# Backplane.net
KiCad netlist of a schematic drawn in EAGLE
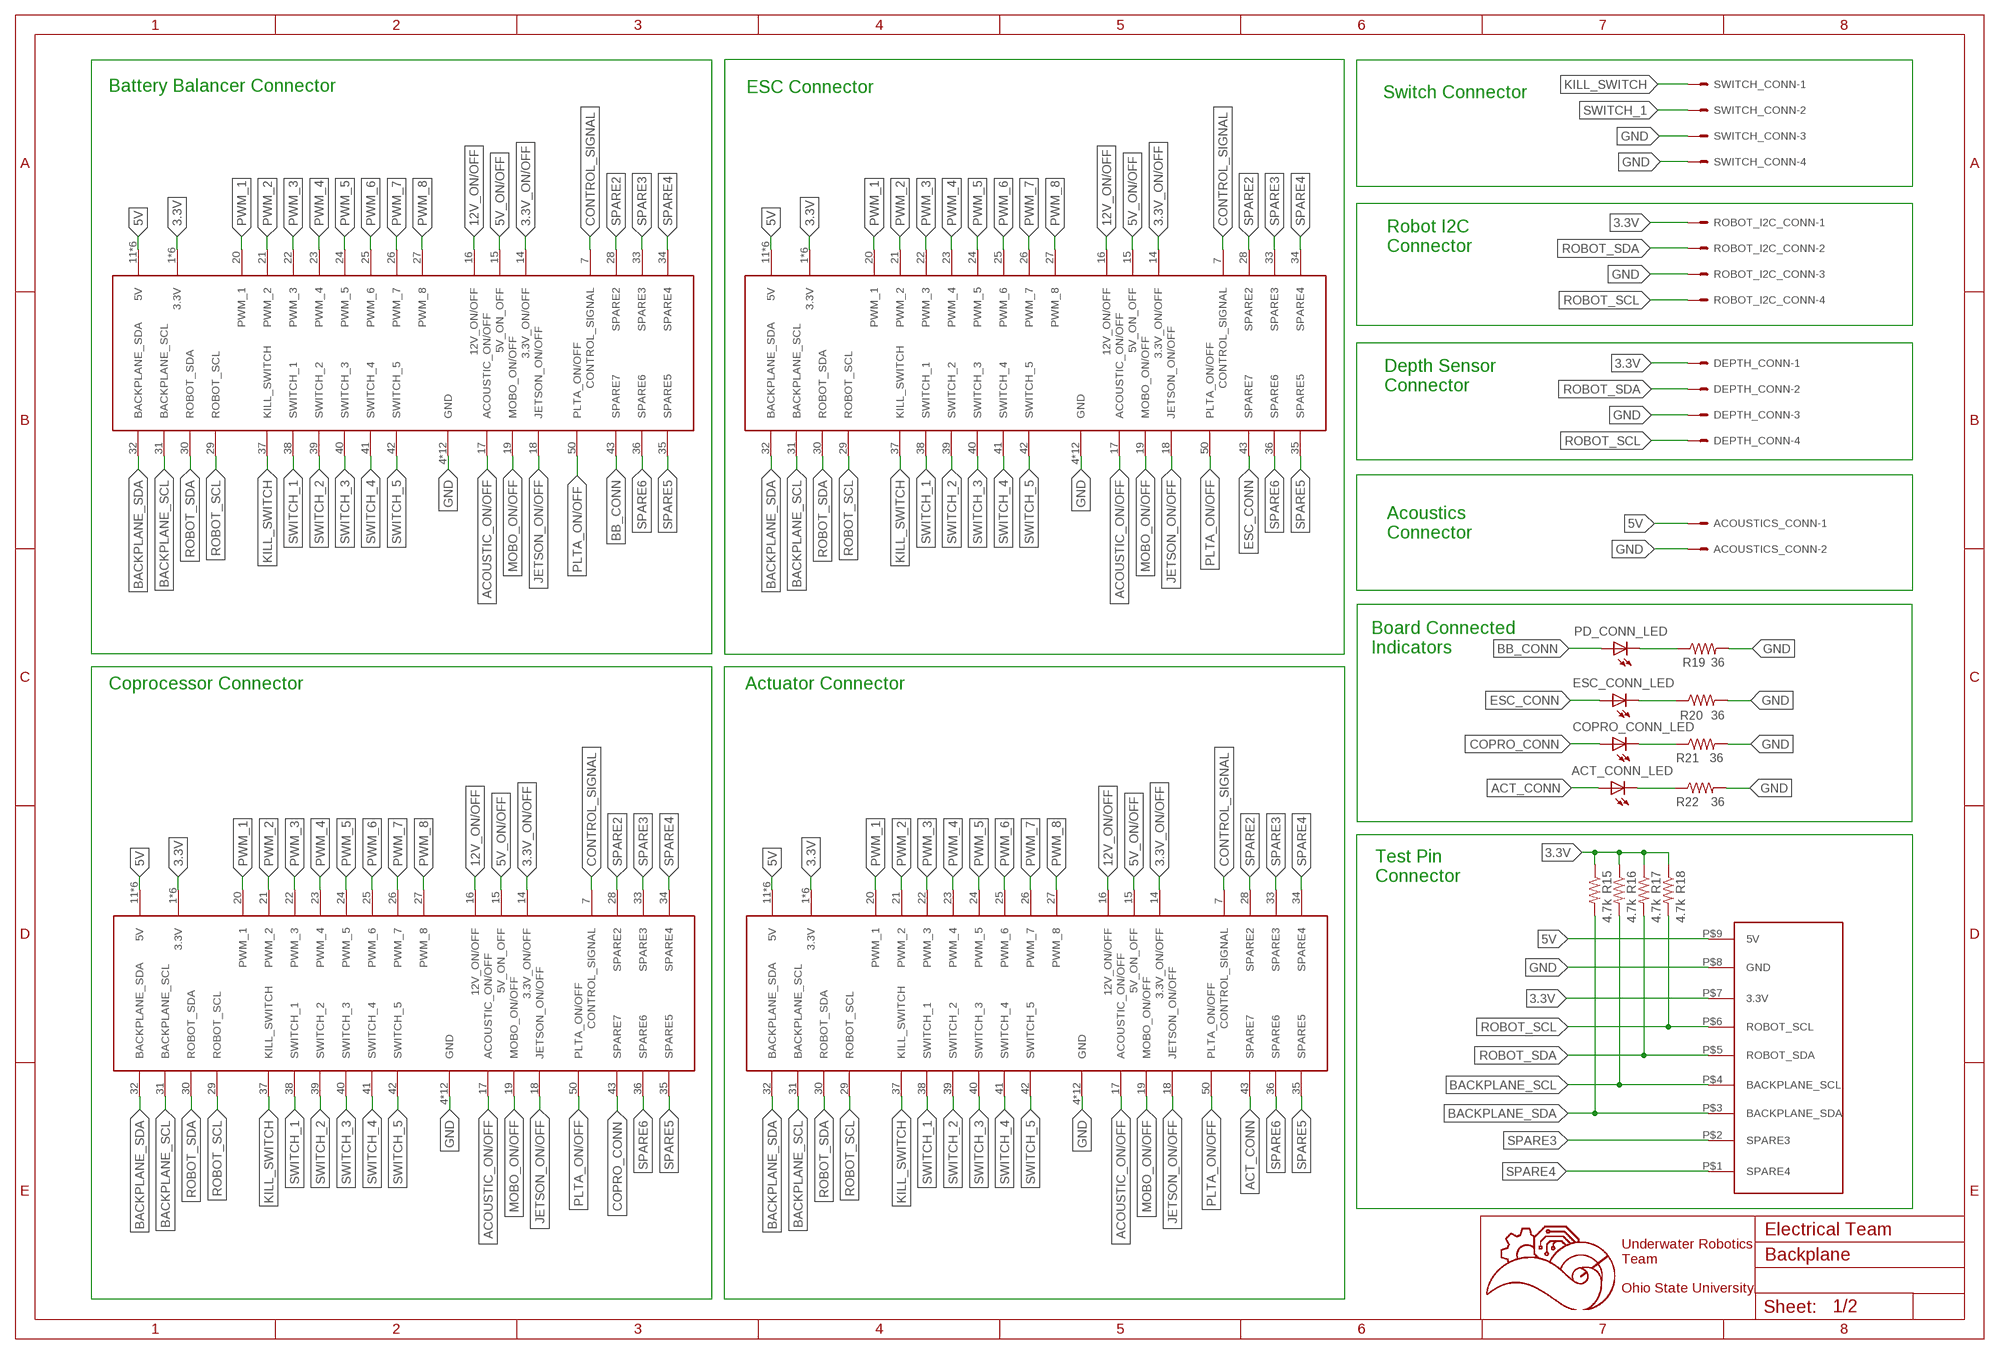
[diagram p0: schematic, sheet 1]
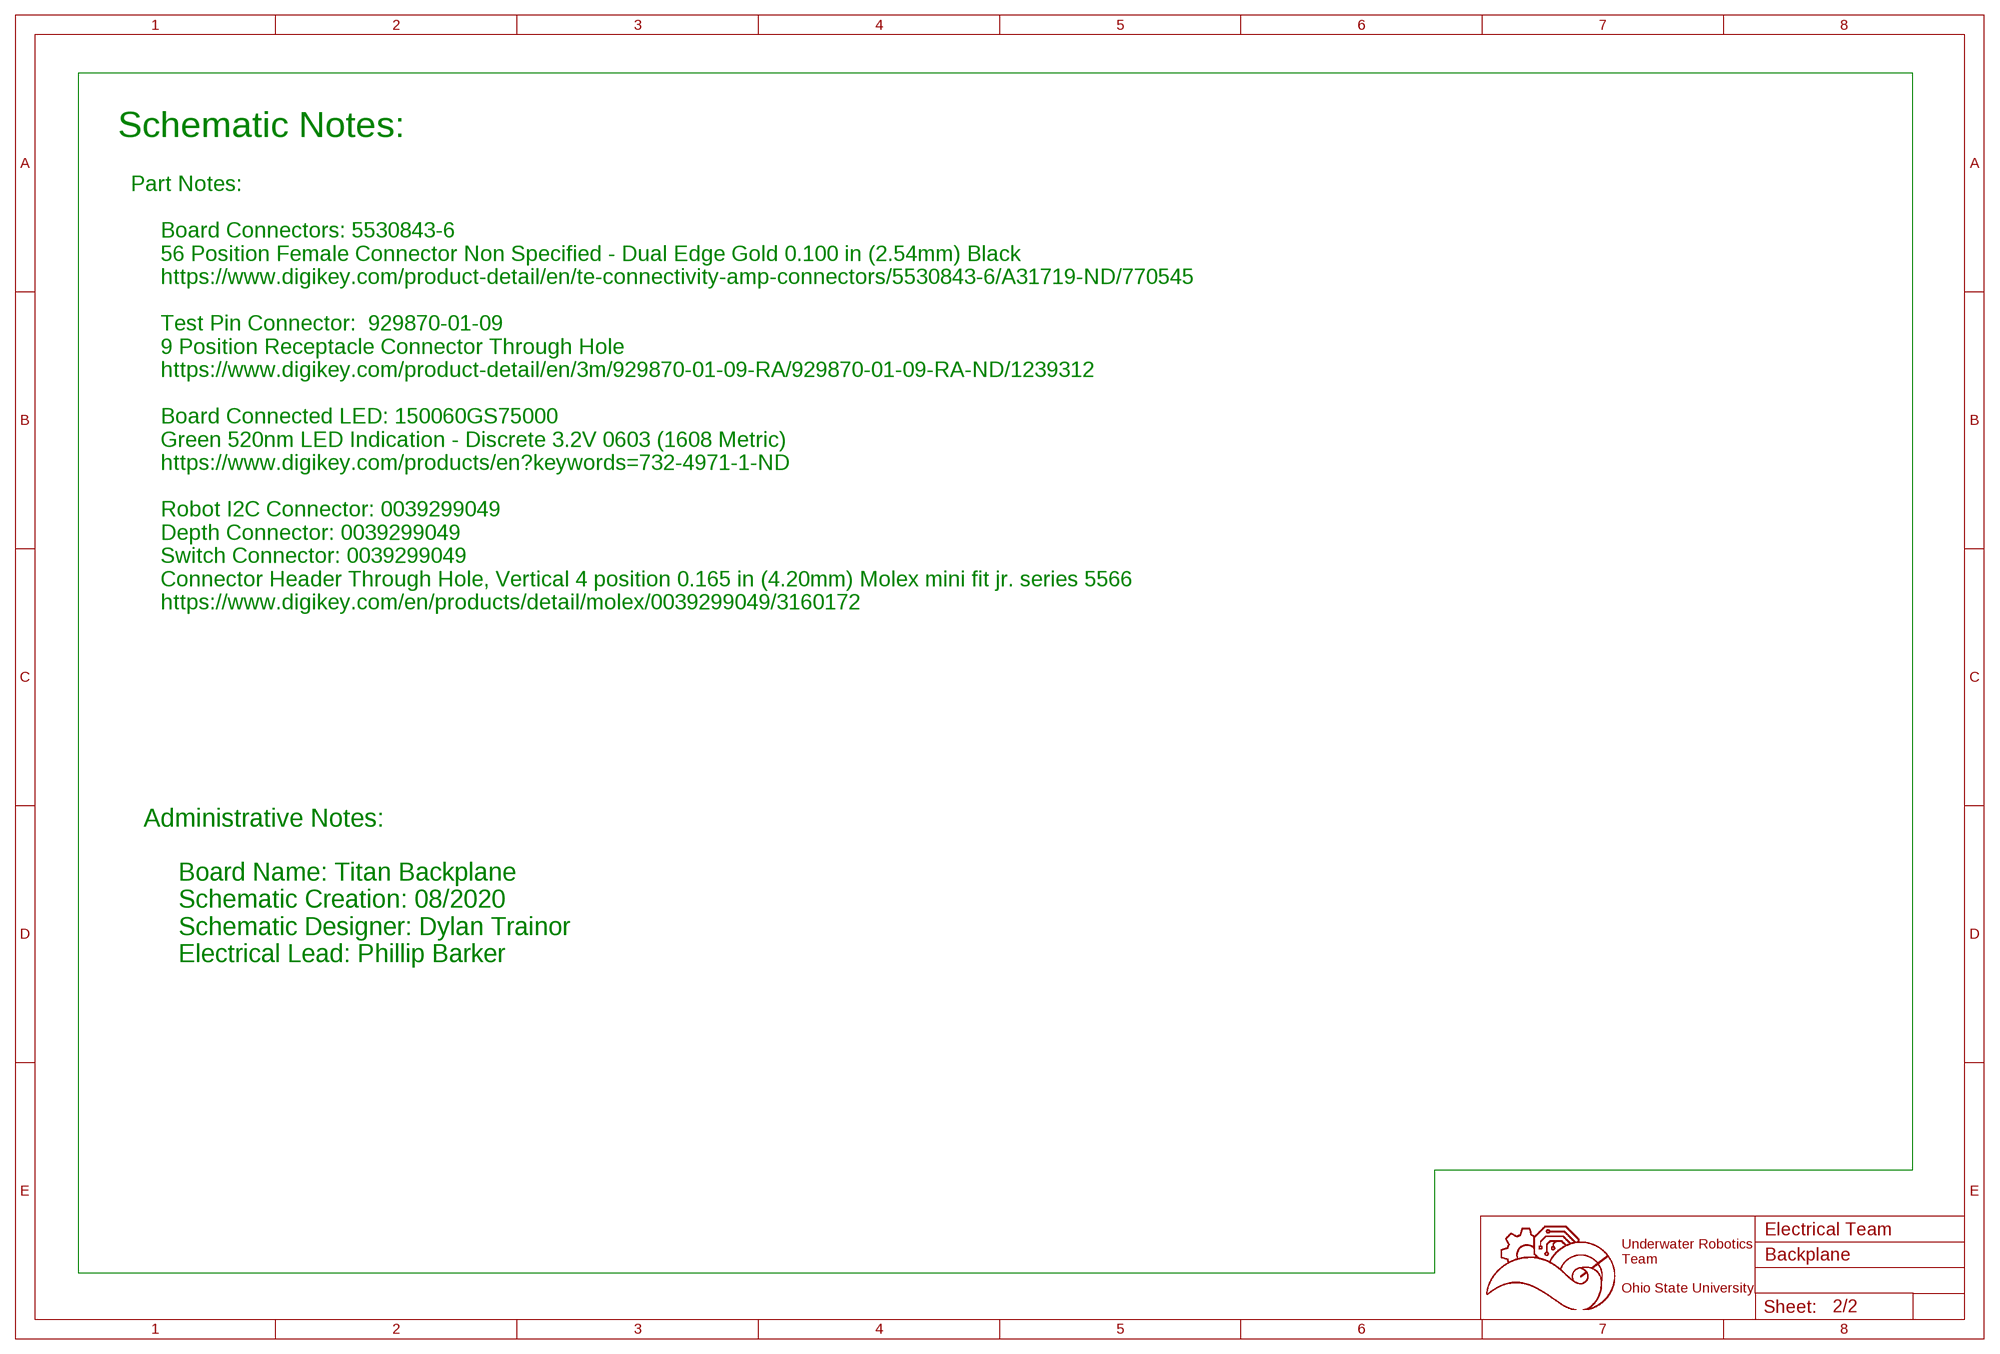
[diagram p1: schematic, sheet 2]

(export (version "E")
  (design (tool "Eeschema 10.0.6"))
  (components
    (comp (ref "ACOUSTICS_CONN")
      (value "555X-2V")
      (footprint "eagle-import:5566-2")
      (libsource (lib "eagle-import") (part "555X-2V"))
    )
    (comp (ref "ACT_CONN_LED")
      (value "LEDCHIP-LED0603")
      (footprint "eagle-import:CHIP-LED0603")
      (libsource (lib "eagle-import") (part "LEDCHIP-LED0603"))
    )
    (comp (ref "COPRO_CONN_LED")
      (value "LEDCHIP-LED0603")
      (footprint "eagle-import:CHIP-LED0603")
      (libsource (lib "eagle-import") (part "LEDCHIP-LED0603"))
    )
    (comp (ref "DEPTH_CONN")
      (value "555X-4V")
      (footprint "eagle-import:5566-4")
      (libsource (lib "eagle-import") (part "555X-4V"))
    )
    (comp (ref "ESC_CONN_LED")
      (value "LEDCHIP-LED0603")
      (footprint "eagle-import:CHIP-LED0603")
      (libsource (lib "eagle-import") (part "LEDCHIP-LED0603"))
    )
    (comp (ref "PD_CONN_LED")
      (value "LEDCHIP-LED0603")
      (footprint "eagle-import:CHIP-LED0603")
      (libsource (lib "eagle-import") (part "LEDCHIP-LED0603"))
    )
    (comp (ref "R15")
      (value "4.7k")
      (footprint "eagle-import:R0603")
      (libsource (lib "eagle-import") (part "R-US_R0603"))
    )
    (comp (ref "R16")
      (value "4.7k")
      (footprint "eagle-import:R0603")
      (libsource (lib "eagle-import") (part "R-US_R0603"))
    )
    (comp (ref "R17")
      (value "4.7k")
      (footprint "eagle-import:R0603")
      (libsource (lib "eagle-import") (part "R-US_R0603"))
    )
    (comp (ref "R18")
      (value "4.7k")
      (footprint "eagle-import:R0603")
      (libsource (lib "eagle-import") (part "R-US_R0603"))
    )
    (comp (ref "R19")
      (value "36")
      (footprint "eagle-import:R0603")
      (libsource (lib "eagle-import") (part "R-US_R0603"))
    )
    (comp (ref "R20")
      (value "36")
      (footprint "eagle-import:R0603")
      (libsource (lib "eagle-import") (part "R-US_R0603"))
    )
    (comp (ref "R21")
      (value "36")
      (footprint "eagle-import:R0603")
      (libsource (lib "eagle-import") (part "R-US_R0603"))
    )
    (comp (ref "R22")
      (value "36")
      (footprint "eagle-import:R0603")
      (libsource (lib "eagle-import") (part "R-US_R0603"))
    )
    (comp (ref "ROBOT_I2C_CONN")
      (value "555X-4V")
      (footprint "eagle-import:5566-4")
      (libsource (lib "eagle-import") (part "555X-4V"))
    )
    (comp (ref "SWITCH_CONN")
      (value "555X-4V")
      (footprint "eagle-import:5566-4")
      (libsource (lib "eagle-import") (part "555X-4V"))
    )
    (comp (ref "TESTPIN_CONNECTOR")
      (value "929870-01-09_4")
      (footprint "eagle-import:929852-01-09_1ROW")
      (libsource (lib "eagle-import") (part "929870-01-09_4"))
    )
    (comp (ref "U$1")
      (value "5530843-FEMALE")
      (footprint "eagle-import:5530843-6-BACKPLANEMATE")
      (libsource (lib "eagle-import") (part "5530843-FEMALE"))
    )
    (comp (ref "U$2")
      (value "5530843-FEMALE")
      (footprint "eagle-import:5530843-6-BACKPLANEMATE")
      (libsource (lib "eagle-import") (part "5530843-FEMALE"))
    )
    (comp (ref "U$3")
      (value "5530843-FEMALE")
      (footprint "eagle-import:5530843-6-BACKPLANEMATE")
      (libsource (lib "eagle-import") (part "5530843-FEMALE"))
    )
    (comp (ref "U$4")
      (value "5530843-FEMALE")
      (footprint "eagle-import:5530843-6-BACKPLANEMATE")
      (libsource (lib "eagle-import") (part "5530843-FEMALE"))
    )
  )
  (nets
    (net (code "1") (name "3.3V") (class "Default")
      (node (ref "DEPTH_CONN") (pin "1") (pinfunction "S_1") (pintype "passive"))
      (node (ref "R15") (pin "1") (pinfunction "1_1") (pintype "passive"))
      (node (ref "R16") (pin "1") (pinfunction "1_1") (pintype "passive"))
      (node (ref "R17") (pin "1") (pinfunction "1_1") (pintype "passive"))
      (node (ref "R18") (pin "1") (pinfunction "1_1") (pintype "passive"))
      (node (ref "ROBOT_I2C_CONN") (pin "1") (pinfunction "S_1") (pintype "passive"))
      (node (ref "TESTPIN_CONNECTOR") (pin "P$7") (pinfunction "3.3V_P$7") (pintype "bidirectional"))
      (node (ref "U$1") (pin "1") (pinfunction "3.3V_1") (pintype "bidirectional"))
      (node (ref "U$1") (pin "2") (pinfunction "3.3V_2") (pintype "bidirectional"))
      (node (ref "U$1") (pin "3") (pinfunction "3.3V_3") (pintype "bidirectional"))
      (node (ref "U$1") (pin "54") (pinfunction "3.3V_54") (pintype "bidirectional"))
      (node (ref "U$1") (pin "55") (pinfunction "3.3V_55") (pintype "bidirectional"))
      (node (ref "U$1") (pin "56") (pinfunction "3.3V_56") (pintype "bidirectional"))
      (node (ref "U$2") (pin "1") (pinfunction "3.3V_1") (pintype "bidirectional"))
      (node (ref "U$2") (pin "2") (pinfunction "3.3V_2") (pintype "bidirectional"))
      (node (ref "U$2") (pin "3") (pinfunction "3.3V_3") (pintype "bidirectional"))
      (node (ref "U$2") (pin "54") (pinfunction "3.3V_54") (pintype "bidirectional"))
      (node (ref "U$2") (pin "55") (pinfunction "3.3V_55") (pintype "bidirectional"))
      (node (ref "U$2") (pin "56") (pinfunction "3.3V_56") (pintype "bidirectional"))
      (node (ref "U$3") (pin "1") (pinfunction "3.3V_1") (pintype "bidirectional"))
      (node (ref "U$3") (pin "2") (pinfunction "3.3V_2") (pintype "bidirectional"))
      (node (ref "U$3") (pin "3") (pinfunction "3.3V_3") (pintype "bidirectional"))
      (node (ref "U$3") (pin "54") (pinfunction "3.3V_54") (pintype "bidirectional"))
      (node (ref "U$3") (pin "55") (pinfunction "3.3V_55") (pintype "bidirectional"))
      (node (ref "U$3") (pin "56") (pinfunction "3.3V_56") (pintype "bidirectional"))
      (node (ref "U$4") (pin "1") (pinfunction "3.3V_1") (pintype "bidirectional"))
      (node (ref "U$4") (pin "2") (pinfunction "3.3V_2") (pintype "bidirectional"))
      (node (ref "U$4") (pin "3") (pinfunction "3.3V_3") (pintype "bidirectional"))
      (node (ref "U$4") (pin "54") (pinfunction "3.3V_54") (pintype "bidirectional"))
      (node (ref "U$4") (pin "55") (pinfunction "3.3V_55") (pintype "bidirectional"))
      (node (ref "U$4") (pin "56") (pinfunction "3.3V_56") (pintype "bidirectional"))
    )
    (net (code "2") (name "3.3V_ON{slash}OFF") (class "Default")
      (node (ref "U$1") (pin "14") (pinfunction "3.3V_ON/OFF_14") (pintype "bidirectional"))
      (node (ref "U$2") (pin "14") (pinfunction "3.3V_ON/OFF_14") (pintype "bidirectional"))
      (node (ref "U$3") (pin "14") (pinfunction "3.3V_ON/OFF_14") (pintype "bidirectional"))
      (node (ref "U$4") (pin "14") (pinfunction "3.3V_ON/OFF_14") (pintype "bidirectional"))
    )
    (net (code "3") (name "5V") (class "Default")
      (node (ref "ACOUSTICS_CONN") (pin "1") (pinfunction "S_1") (pintype "passive"))
      (node (ref "TESTPIN_CONNECTOR") (pin "P$9") (pinfunction "5V_P$9") (pintype "bidirectional"))
      (node (ref "U$1") (pin "11") (pinfunction "5V_11") (pintype "bidirectional"))
      (node (ref "U$1") (pin "12") (pinfunction "5V_12") (pintype "bidirectional"))
      (node (ref "U$1") (pin "13") (pinfunction "5V_13") (pintype "bidirectional"))
      (node (ref "U$1") (pin "44") (pinfunction "5V_44") (pintype "bidirectional"))
      (node (ref "U$1") (pin "45") (pinfunction "5V_45") (pintype "bidirectional"))
      (node (ref "U$1") (pin "46") (pinfunction "5V_46") (pintype "bidirectional"))
      (node (ref "U$2") (pin "11") (pinfunction "5V_11") (pintype "bidirectional"))
      (node (ref "U$2") (pin "12") (pinfunction "5V_12") (pintype "bidirectional"))
      (node (ref "U$2") (pin "13") (pinfunction "5V_13") (pintype "bidirectional"))
      (node (ref "U$2") (pin "44") (pinfunction "5V_44") (pintype "bidirectional"))
      (node (ref "U$2") (pin "45") (pinfunction "5V_45") (pintype "bidirectional"))
      (node (ref "U$2") (pin "46") (pinfunction "5V_46") (pintype "bidirectional"))
      (node (ref "U$3") (pin "11") (pinfunction "5V_11") (pintype "bidirectional"))
      (node (ref "U$3") (pin "12") (pinfunction "5V_12") (pintype "bidirectional"))
      (node (ref "U$3") (pin "13") (pinfunction "5V_13") (pintype "bidirectional"))
      (node (ref "U$3") (pin "44") (pinfunction "5V_44") (pintype "bidirectional"))
      (node (ref "U$3") (pin "45") (pinfunction "5V_45") (pintype "bidirectional"))
      (node (ref "U$3") (pin "46") (pinfunction "5V_46") (pintype "bidirectional"))
      (node (ref "U$4") (pin "11") (pinfunction "5V_11") (pintype "bidirectional"))
      (node (ref "U$4") (pin "12") (pinfunction "5V_12") (pintype "bidirectional"))
      (node (ref "U$4") (pin "13") (pinfunction "5V_13") (pintype "bidirectional"))
      (node (ref "U$4") (pin "44") (pinfunction "5V_44") (pintype "bidirectional"))
      (node (ref "U$4") (pin "45") (pinfunction "5V_45") (pintype "bidirectional"))
      (node (ref "U$4") (pin "46") (pinfunction "5V_46") (pintype "bidirectional"))
    )
    (net (code "4") (name "5V_ON{slash}OFF") (class "Default")
      (node (ref "U$1") (pin "15") (pinfunction "5V_ON_OFF_15") (pintype "bidirectional"))
      (node (ref "U$2") (pin "15") (pinfunction "5V_ON_OFF_15") (pintype "bidirectional"))
      (node (ref "U$3") (pin "15") (pinfunction "5V_ON_OFF_15") (pintype "bidirectional"))
      (node (ref "U$4") (pin "15") (pinfunction "5V_ON_OFF_15") (pintype "bidirectional"))
    )
    (net (code "5") (name "12V_ON{slash}OFF") (class "Default")
      (node (ref "U$1") (pin "16") (pinfunction "12V_ON/OFF_16") (pintype "bidirectional"))
      (node (ref "U$2") (pin "16") (pinfunction "12V_ON/OFF_16") (pintype "bidirectional"))
      (node (ref "U$3") (pin "16") (pinfunction "12V_ON/OFF_16") (pintype "bidirectional"))
      (node (ref "U$4") (pin "16") (pinfunction "12V_ON/OFF_16") (pintype "bidirectional"))
    )
    (net (code "6") (name "ACOUSTIC_ON{slash}OFF") (class "Default")
      (node (ref "U$1") (pin "17") (pinfunction "ACOUSTIC_ON/OFF_17") (pintype "bidirectional"))
      (node (ref "U$2") (pin "17") (pinfunction "ACOUSTIC_ON/OFF_17") (pintype "bidirectional"))
      (node (ref "U$3") (pin "17") (pinfunction "ACOUSTIC_ON/OFF_17") (pintype "bidirectional"))
      (node (ref "U$4") (pin "17") (pinfunction "ACOUSTIC_ON/OFF_17") (pintype "bidirectional"))
    )
    (net (code "7") (name "ACT_CONN") (class "Default")
      (node (ref "ACT_CONN_LED") (pin "A") (pinfunction "A_A") (pintype "passive"))
      (node (ref "U$4") (pin "43") (pinfunction "SPARE7_43") (pintype "bidirectional"))
    )
    (net (code "8") (name "BACKPLANE_SCL") (class "Default")
      (node (ref "R16") (pin "2") (pinfunction "2_2") (pintype "passive"))
      (node (ref "TESTPIN_CONNECTOR") (pin "P$4") (pinfunction "BACKPLANE_SCL_P$4") (pintype "bidirectional"))
      (node (ref "U$1") (pin "31") (pinfunction "BACKPLANE_SCL_31") (pintype "bidirectional"))
      (node (ref "U$2") (pin "31") (pinfunction "BACKPLANE_SCL_31") (pintype "bidirectional"))
      (node (ref "U$3") (pin "31") (pinfunction "BACKPLANE_SCL_31") (pintype "bidirectional"))
      (node (ref "U$4") (pin "31") (pinfunction "BACKPLANE_SCL_31") (pintype "bidirectional"))
    )
    (net (code "9") (name "BACKPLANE_SDA") (class "Default")
      (node (ref "R15") (pin "2") (pinfunction "2_2") (pintype "passive"))
      (node (ref "TESTPIN_CONNECTOR") (pin "P$3") (pinfunction "BACKPLANE_SDA_P$3") (pintype "bidirectional"))
      (node (ref "U$1") (pin "32") (pinfunction "BACKPLANE_SDA_32") (pintype "bidirectional"))
      (node (ref "U$2") (pin "32") (pinfunction "BACKPLANE_SDA_32") (pintype "bidirectional"))
      (node (ref "U$3") (pin "32") (pinfunction "BACKPLANE_SDA_32") (pintype "bidirectional"))
      (node (ref "U$4") (pin "32") (pinfunction "BACKPLANE_SDA_32") (pintype "bidirectional"))
    )
    (net (code "10") (name "BB_CONN") (class "Default")
      (node (ref "PD_CONN_LED") (pin "A") (pinfunction "A_A") (pintype "passive"))
      (node (ref "U$1") (pin "43") (pinfunction "SPARE7_43") (pintype "bidirectional"))
    )
    (net (code "11") (name "CONTROL_SIGNAL") (class "Default")
      (node (ref "U$1") (pin "7") (pinfunction "CONTROL_SIGNAL_7") (pintype "bidirectional"))
      (node (ref "U$2") (pin "7") (pinfunction "CONTROL_SIGNAL_7") (pintype "bidirectional"))
      (node (ref "U$3") (pin "7") (pinfunction "CONTROL_SIGNAL_7") (pintype "bidirectional"))
      (node (ref "U$4") (pin "7") (pinfunction "CONTROL_SIGNAL_7") (pintype "bidirectional"))
    )
    (net (code "12") (name "COPRO_CONN") (class "Default")
      (node (ref "COPRO_CONN_LED") (pin "A") (pinfunction "A_A") (pintype "passive"))
      (node (ref "U$3") (pin "43") (pinfunction "SPARE7_43") (pintype "bidirectional"))
    )
    (net (code "13") (name "ESC_CONN") (class "Default")
      (node (ref "ESC_CONN_LED") (pin "A") (pinfunction "A_A") (pintype "passive"))
      (node (ref "U$2") (pin "43") (pinfunction "SPARE7_43") (pintype "bidirectional"))
    )
    (net (code "14") (name "GND") (class "Default")
      (node (ref "ACOUSTICS_CONN") (pin "2") (pinfunction "S_2") (pintype "passive"))
      (node (ref "DEPTH_CONN") (pin "3") (pinfunction "S_3") (pintype "passive"))
      (node (ref "R19") (pin "2") (pinfunction "2_2") (pintype "passive"))
      (node (ref "R20") (pin "2") (pinfunction "2_2") (pintype "passive"))
      (node (ref "R21") (pin "2") (pinfunction "2_2") (pintype "passive"))
      (node (ref "R22") (pin "2") (pinfunction "2_2") (pintype "passive"))
      (node (ref "ROBOT_I2C_CONN") (pin "3") (pinfunction "S_3") (pintype "passive"))
      (node (ref "SWITCH_CONN") (pin "3") (pinfunction "S_3") (pintype "passive"))
      (node (ref "SWITCH_CONN") (pin "4") (pinfunction "S_4") (pintype "passive"))
      (node (ref "TESTPIN_CONNECTOR") (pin "P$8") (pinfunction "GND_P$8") (pintype "bidirectional"))
      (node (ref "U$1") (pin "10") (pinfunction "GND_10") (pintype "bidirectional"))
      (node (ref "U$1") (pin "4") (pinfunction "GND_4") (pintype "bidirectional"))
      (node (ref "U$1") (pin "47") (pinfunction "GND_47") (pintype "bidirectional"))
      (node (ref "U$1") (pin "48") (pinfunction "GND_48") (pintype "bidirectional"))
      (node (ref "U$1") (pin "49") (pinfunction "GND_49") (pintype "bidirectional"))
      (node (ref "U$1") (pin "5") (pinfunction "GND_5") (pintype "bidirectional"))
      (node (ref "U$1") (pin "51") (pinfunction "GND_51") (pintype "bidirectional"))
      (node (ref "U$1") (pin "52") (pinfunction "GND_52") (pintype "bidirectional"))
      (node (ref "U$1") (pin "53") (pinfunction "GND_53") (pintype "bidirectional"))
      (node (ref "U$1") (pin "6") (pinfunction "GND_6") (pintype "bidirectional"))
      (node (ref "U$1") (pin "8") (pinfunction "GND_8") (pintype "bidirectional"))
      (node (ref "U$1") (pin "9") (pinfunction "GND_9") (pintype "bidirectional"))
      (node (ref "U$2") (pin "10") (pinfunction "GND_10") (pintype "bidirectional"))
      (node (ref "U$2") (pin "4") (pinfunction "GND_4") (pintype "bidirectional"))
      (node (ref "U$2") (pin "47") (pinfunction "GND_47") (pintype "bidirectional"))
      (node (ref "U$2") (pin "48") (pinfunction "GND_48") (pintype "bidirectional"))
      (node (ref "U$2") (pin "49") (pinfunction "GND_49") (pintype "bidirectional"))
      (node (ref "U$2") (pin "5") (pinfunction "GND_5") (pintype "bidirectional"))
      (node (ref "U$2") (pin "51") (pinfunction "GND_51") (pintype "bidirectional"))
      (node (ref "U$2") (pin "52") (pinfunction "GND_52") (pintype "bidirectional"))
      (node (ref "U$2") (pin "53") (pinfunction "GND_53") (pintype "bidirectional"))
      (node (ref "U$2") (pin "6") (pinfunction "GND_6") (pintype "bidirectional"))
      (node (ref "U$2") (pin "8") (pinfunction "GND_8") (pintype "bidirectional"))
      (node (ref "U$2") (pin "9") (pinfunction "GND_9") (pintype "bidirectional"))
      (node (ref "U$3") (pin "10") (pinfunction "GND_10") (pintype "bidirectional"))
      (node (ref "U$3") (pin "4") (pinfunction "GND_4") (pintype "bidirectional"))
      (node (ref "U$3") (pin "47") (pinfunction "GND_47") (pintype "bidirectional"))
      (node (ref "U$3") (pin "48") (pinfunction "GND_48") (pintype "bidirectional"))
      (node (ref "U$3") (pin "49") (pinfunction "GND_49") (pintype "bidirectional"))
      (node (ref "U$3") (pin "5") (pinfunction "GND_5") (pintype "bidirectional"))
      (node (ref "U$3") (pin "51") (pinfunction "GND_51") (pintype "bidirectional"))
      (node (ref "U$3") (pin "52") (pinfunction "GND_52") (pintype "bidirectional"))
      (node (ref "U$3") (pin "53") (pinfunction "GND_53") (pintype "bidirectional"))
      (node (ref "U$3") (pin "6") (pinfunction "GND_6") (pintype "bidirectional"))
      (node (ref "U$3") (pin "8") (pinfunction "GND_8") (pintype "bidirectional"))
      (node (ref "U$3") (pin "9") (pinfunction "GND_9") (pintype "bidirectional"))
      (node (ref "U$4") (pin "10") (pinfunction "GND_10") (pintype "bidirectional"))
      (node (ref "U$4") (pin "4") (pinfunction "GND_4") (pintype "bidirectional"))
      (node (ref "U$4") (pin "47") (pinfunction "GND_47") (pintype "bidirectional"))
      (node (ref "U$4") (pin "48") (pinfunction "GND_48") (pintype "bidirectional"))
      (node (ref "U$4") (pin "49") (pinfunction "GND_49") (pintype "bidirectional"))
      (node (ref "U$4") (pin "5") (pinfunction "GND_5") (pintype "bidirectional"))
      (node (ref "U$4") (pin "51") (pinfunction "GND_51") (pintype "bidirectional"))
      (node (ref "U$4") (pin "52") (pinfunction "GND_52") (pintype "bidirectional"))
      (node (ref "U$4") (pin "53") (pinfunction "GND_53") (pintype "bidirectional"))
      (node (ref "U$4") (pin "6") (pinfunction "GND_6") (pintype "bidirectional"))
      (node (ref "U$4") (pin "8") (pinfunction "GND_8") (pintype "bidirectional"))
      (node (ref "U$4") (pin "9") (pinfunction "GND_9") (pintype "bidirectional"))
    )
    (net (code "15") (name "JETSON_ON{slash}OFF") (class "Default")
      (node (ref "U$1") (pin "18") (pinfunction "JETSON_ON/OFF_18") (pintype "bidirectional"))
      (node (ref "U$2") (pin "18") (pinfunction "JETSON_ON/OFF_18") (pintype "bidirectional"))
      (node (ref "U$3") (pin "18") (pinfunction "JETSON_ON/OFF_18") (pintype "bidirectional"))
      (node (ref "U$4") (pin "18") (pinfunction "JETSON_ON/OFF_18") (pintype "bidirectional"))
    )
    (net (code "16") (name "KILL_SWITCH") (class "Default")
      (node (ref "SWITCH_CONN") (pin "1") (pinfunction "S_1") (pintype "passive"))
      (node (ref "U$1") (pin "37") (pinfunction "KILL_SWITCH_37") (pintype "output"))
      (node (ref "U$2") (pin "37") (pinfunction "KILL_SWITCH_37") (pintype "output"))
      (node (ref "U$3") (pin "37") (pinfunction "KILL_SWITCH_37") (pintype "output"))
      (node (ref "U$4") (pin "37") (pinfunction "KILL_SWITCH_37") (pintype "output"))
    )
    (net (code "17") (name "MOBO_ON{slash}OFF") (class "Default")
      (node (ref "U$1") (pin "19") (pinfunction "MOBO_ON/OFF_19") (pintype "bidirectional"))
      (node (ref "U$2") (pin "19") (pinfunction "MOBO_ON/OFF_19") (pintype "bidirectional"))
      (node (ref "U$3") (pin "19") (pinfunction "MOBO_ON/OFF_19") (pintype "bidirectional"))
      (node (ref "U$4") (pin "19") (pinfunction "MOBO_ON/OFF_19") (pintype "bidirectional"))
    )
    (net (code "18") (name "Net-(ACT_CONN_LED-PadC)") (class "Default")
      (node (ref "ACT_CONN_LED") (pin "C") (pinfunction "C_C") (pintype "passive"))
      (node (ref "R22") (pin "1") (pinfunction "1_1") (pintype "passive"))
    )
    (net (code "19") (name "Net-(COPRO_CONN_LED-PadC)") (class "Default")
      (node (ref "COPRO_CONN_LED") (pin "C") (pinfunction "C_C") (pintype "passive"))
      (node (ref "R21") (pin "1") (pinfunction "1_1") (pintype "passive"))
    )
    (net (code "20") (name "Net-(ESC_CONN_LED-PadC)") (class "Default")
      (node (ref "ESC_CONN_LED") (pin "C") (pinfunction "C_C") (pintype "passive"))
      (node (ref "R20") (pin "1") (pinfunction "1_1") (pintype "passive"))
    )
    (net (code "21") (name "Net-(PD_CONN_LED-PadC)") (class "Default")
      (node (ref "PD_CONN_LED") (pin "C") (pinfunction "C_C") (pintype "passive"))
      (node (ref "R19") (pin "1") (pinfunction "1_1") (pintype "passive"))
    )
    (net (code "22") (name "PLTA_ON{slash}OFF") (class "Default")
      (node (ref "U$1") (pin "50") (pinfunction "PLTA_ON/OFF_50") (pintype "bidirectional"))
      (node (ref "U$2") (pin "50") (pinfunction "PLTA_ON/OFF_50") (pintype "bidirectional"))
      (node (ref "U$3") (pin "50") (pinfunction "PLTA_ON/OFF_50") (pintype "bidirectional"))
      (node (ref "U$4") (pin "50") (pinfunction "PLTA_ON/OFF_50") (pintype "bidirectional"))
    )
    (net (code "23") (name "PWM_1") (class "Default")
      (node (ref "U$1") (pin "20") (pinfunction "PWM_1_20") (pintype "bidirectional"))
      (node (ref "U$2") (pin "20") (pinfunction "PWM_1_20") (pintype "bidirectional"))
      (node (ref "U$3") (pin "20") (pinfunction "PWM_1_20") (pintype "bidirectional"))
      (node (ref "U$4") (pin "20") (pinfunction "PWM_1_20") (pintype "bidirectional"))
    )
    (net (code "24") (name "PWM_2") (class "Default")
      (node (ref "U$1") (pin "21") (pinfunction "PWM_2_21") (pintype "bidirectional"))
      (node (ref "U$2") (pin "21") (pinfunction "PWM_2_21") (pintype "bidirectional"))
      (node (ref "U$3") (pin "21") (pinfunction "PWM_2_21") (pintype "bidirectional"))
      (node (ref "U$4") (pin "21") (pinfunction "PWM_2_21") (pintype "bidirectional"))
    )
    (net (code "25") (name "PWM_3") (class "Default")
      (node (ref "U$1") (pin "22") (pinfunction "PWM_3_22") (pintype "bidirectional"))
      (node (ref "U$2") (pin "22") (pinfunction "PWM_3_22") (pintype "bidirectional"))
      (node (ref "U$3") (pin "22") (pinfunction "PWM_3_22") (pintype "bidirectional"))
      (node (ref "U$4") (pin "22") (pinfunction "PWM_3_22") (pintype "bidirectional"))
    )
    (net (code "26") (name "PWM_4") (class "Default")
      (node (ref "U$1") (pin "23") (pinfunction "PWM_4_23") (pintype "bidirectional"))
      (node (ref "U$2") (pin "23") (pinfunction "PWM_4_23") (pintype "bidirectional"))
      (node (ref "U$3") (pin "23") (pinfunction "PWM_4_23") (pintype "bidirectional"))
      (node (ref "U$4") (pin "23") (pinfunction "PWM_4_23") (pintype "bidirectional"))
    )
    (net (code "27") (name "PWM_5") (class "Default")
      (node (ref "U$1") (pin "24") (pinfunction "PWM_5_24") (pintype "bidirectional"))
      (node (ref "U$2") (pin "24") (pinfunction "PWM_5_24") (pintype "bidirectional"))
      (node (ref "U$3") (pin "24") (pinfunction "PWM_5_24") (pintype "bidirectional"))
      (node (ref "U$4") (pin "24") (pinfunction "PWM_5_24") (pintype "bidirectional"))
    )
    (net (code "28") (name "PWM_6") (class "Default")
      (node (ref "U$1") (pin "25") (pinfunction "PWM_6_25") (pintype "bidirectional"))
      (node (ref "U$2") (pin "25") (pinfunction "PWM_6_25") (pintype "bidirectional"))
      (node (ref "U$3") (pin "25") (pinfunction "PWM_6_25") (pintype "bidirectional"))
      (node (ref "U$4") (pin "25") (pinfunction "PWM_6_25") (pintype "bidirectional"))
    )
    (net (code "29") (name "PWM_7") (class "Default")
      (node (ref "U$1") (pin "26") (pinfunction "PWM_7_26") (pintype "bidirectional"))
      (node (ref "U$2") (pin "26") (pinfunction "PWM_7_26") (pintype "bidirectional"))
      (node (ref "U$3") (pin "26") (pinfunction "PWM_7_26") (pintype "bidirectional"))
      (node (ref "U$4") (pin "26") (pinfunction "PWM_7_26") (pintype "bidirectional"))
    )
    (net (code "30") (name "PWM_8") (class "Default")
      (node (ref "U$1") (pin "27") (pinfunction "PWM_8_27") (pintype "bidirectional"))
      (node (ref "U$2") (pin "27") (pinfunction "PWM_8_27") (pintype "bidirectional"))
      (node (ref "U$3") (pin "27") (pinfunction "PWM_8_27") (pintype "bidirectional"))
      (node (ref "U$4") (pin "27") (pinfunction "PWM_8_27") (pintype "bidirectional"))
    )
    (net (code "31") (name "ROBOT_SCL") (class "Default")
      (node (ref "DEPTH_CONN") (pin "4") (pinfunction "S_4") (pintype "passive"))
      (node (ref "R18") (pin "2") (pinfunction "2_2") (pintype "passive"))
      (node (ref "ROBOT_I2C_CONN") (pin "4") (pinfunction "S_4") (pintype "passive"))
      (node (ref "TESTPIN_CONNECTOR") (pin "P$6") (pinfunction "ROBOT_SCL_P$6") (pintype "bidirectional"))
      (node (ref "U$1") (pin "29") (pinfunction "ROBOT_SCL_29") (pintype "bidirectional"))
      (node (ref "U$2") (pin "29") (pinfunction "ROBOT_SCL_29") (pintype "bidirectional"))
      (node (ref "U$3") (pin "29") (pinfunction "ROBOT_SCL_29") (pintype "bidirectional"))
      (node (ref "U$4") (pin "29") (pinfunction "ROBOT_SCL_29") (pintype "bidirectional"))
    )
    (net (code "32") (name "ROBOT_SDA") (class "Default")
      (node (ref "DEPTH_CONN") (pin "2") (pinfunction "S_2") (pintype "passive"))
      (node (ref "R17") (pin "2") (pinfunction "2_2") (pintype "passive"))
      (node (ref "ROBOT_I2C_CONN") (pin "2") (pinfunction "S_2") (pintype "passive"))
      (node (ref "TESTPIN_CONNECTOR") (pin "P$5") (pinfunction "ROBOT_SDA_P$5") (pintype "bidirectional"))
      (node (ref "U$1") (pin "30") (pinfunction "ROBOT_SDA_30") (pintype "bidirectional"))
      (node (ref "U$2") (pin "30") (pinfunction "ROBOT_SDA_30") (pintype "bidirectional"))
      (node (ref "U$3") (pin "30") (pinfunction "ROBOT_SDA_30") (pintype "bidirectional"))
      (node (ref "U$4") (pin "30") (pinfunction "ROBOT_SDA_30") (pintype "bidirectional"))
    )
    (net (code "33") (name "SPARE2") (class "Default")
      (node (ref "U$1") (pin "28") (pinfunction "SPARE2_28") (pintype "bidirectional"))
      (node (ref "U$2") (pin "28") (pinfunction "SPARE2_28") (pintype "bidirectional"))
      (node (ref "U$3") (pin "28") (pinfunction "SPARE2_28") (pintype "bidirectional"))
      (node (ref "U$4") (pin "28") (pinfunction "SPARE2_28") (pintype "bidirectional"))
    )
    (net (code "34") (name "SPARE3") (class "Default")
      (node (ref "TESTPIN_CONNECTOR") (pin "P$2") (pinfunction "SPARE3_P$2") (pintype "bidirectional"))
      (node (ref "U$1") (pin "33") (pinfunction "SPARE3_33") (pintype "bidirectional"))
      (node (ref "U$2") (pin "33") (pinfunction "SPARE3_33") (pintype "bidirectional"))
      (node (ref "U$3") (pin "33") (pinfunction "SPARE3_33") (pintype "bidirectional"))
      (node (ref "U$4") (pin "33") (pinfunction "SPARE3_33") (pintype "bidirectional"))
    )
    (net (code "35") (name "SPARE4") (class "Default")
      (node (ref "TESTPIN_CONNECTOR") (pin "P$1") (pinfunction "SPARE4_P$1") (pintype "bidirectional"))
      (node (ref "U$1") (pin "34") (pinfunction "SPARE4_34") (pintype "bidirectional"))
      (node (ref "U$2") (pin "34") (pinfunction "SPARE4_34") (pintype "bidirectional"))
      (node (ref "U$3") (pin "34") (pinfunction "SPARE4_34") (pintype "bidirectional"))
      (node (ref "U$4") (pin "34") (pinfunction "SPARE4_34") (pintype "bidirectional"))
    )
    (net (code "36") (name "SPARE5") (class "Default")
      (node (ref "U$1") (pin "35") (pinfunction "SPARE5_35") (pintype "bidirectional"))
      (node (ref "U$2") (pin "35") (pinfunction "SPARE5_35") (pintype "bidirectional"))
      (node (ref "U$3") (pin "35") (pinfunction "SPARE5_35") (pintype "bidirectional"))
      (node (ref "U$4") (pin "35") (pinfunction "SPARE5_35") (pintype "bidirectional"))
    )
    (net (code "37") (name "SPARE6") (class "Default")
      (node (ref "U$1") (pin "36") (pinfunction "SPARE6_36") (pintype "bidirectional"))
      (node (ref "U$2") (pin "36") (pinfunction "SPARE6_36") (pintype "bidirectional"))
      (node (ref "U$3") (pin "36") (pinfunction "SPARE6_36") (pintype "bidirectional"))
      (node (ref "U$4") (pin "36") (pinfunction "SPARE6_36") (pintype "bidirectional"))
    )
    (net (code "38") (name "SWITCH_1") (class "Default")
      (node (ref "SWITCH_CONN") (pin "2") (pinfunction "S_2") (pintype "passive"))
      (node (ref "U$1") (pin "38") (pinfunction "SWITCH_1_38") (pintype "output"))
      (node (ref "U$2") (pin "38") (pinfunction "SWITCH_1_38") (pintype "output"))
      (node (ref "U$3") (pin "38") (pinfunction "SWITCH_1_38") (pintype "output"))
      (node (ref "U$4") (pin "38") (pinfunction "SWITCH_1_38") (pintype "output"))
    )
    (net (code "39") (name "SWITCH_2") (class "Default")
      (node (ref "U$1") (pin "39") (pinfunction "SWITCH_2_39") (pintype "output"))
      (node (ref "U$2") (pin "39") (pinfunction "SWITCH_2_39") (pintype "output"))
      (node (ref "U$3") (pin "39") (pinfunction "SWITCH_2_39") (pintype "output"))
      (node (ref "U$4") (pin "39") (pinfunction "SWITCH_2_39") (pintype "output"))
    )
    (net (code "40") (name "SWITCH_3") (class "Default")
      (node (ref "U$1") (pin "40") (pinfunction "SWITCH_3_40") (pintype "output"))
      (node (ref "U$2") (pin "40") (pinfunction "SWITCH_3_40") (pintype "output"))
      (node (ref "U$3") (pin "40") (pinfunction "SWITCH_3_40") (pintype "output"))
      (node (ref "U$4") (pin "40") (pinfunction "SWITCH_3_40") (pintype "output"))
    )
    (net (code "41") (name "SWITCH_4") (class "Default")
      (node (ref "U$1") (pin "41") (pinfunction "SWITCH_4_41") (pintype "output"))
      (node (ref "U$2") (pin "41") (pinfunction "SWITCH_4_41") (pintype "output"))
      (node (ref "U$3") (pin "41") (pinfunction "SWITCH_4_41") (pintype "output"))
      (node (ref "U$4") (pin "41") (pinfunction "SWITCH_4_41") (pintype "output"))
    )
    (net (code "42") (name "SWITCH_5") (class "Default")
      (node (ref "U$1") (pin "42") (pinfunction "SWITCH_5_42") (pintype "output"))
      (node (ref "U$2") (pin "42") (pinfunction "SWITCH_5_42") (pintype "output"))
      (node (ref "U$3") (pin "42") (pinfunction "SWITCH_5_42") (pintype "output"))
      (node (ref "U$4") (pin "42") (pinfunction "SWITCH_5_42") (pintype "output"))
    )
  )
)
